# Soal_1.net
KiCad netlist of a schematic drawn in EAGLE
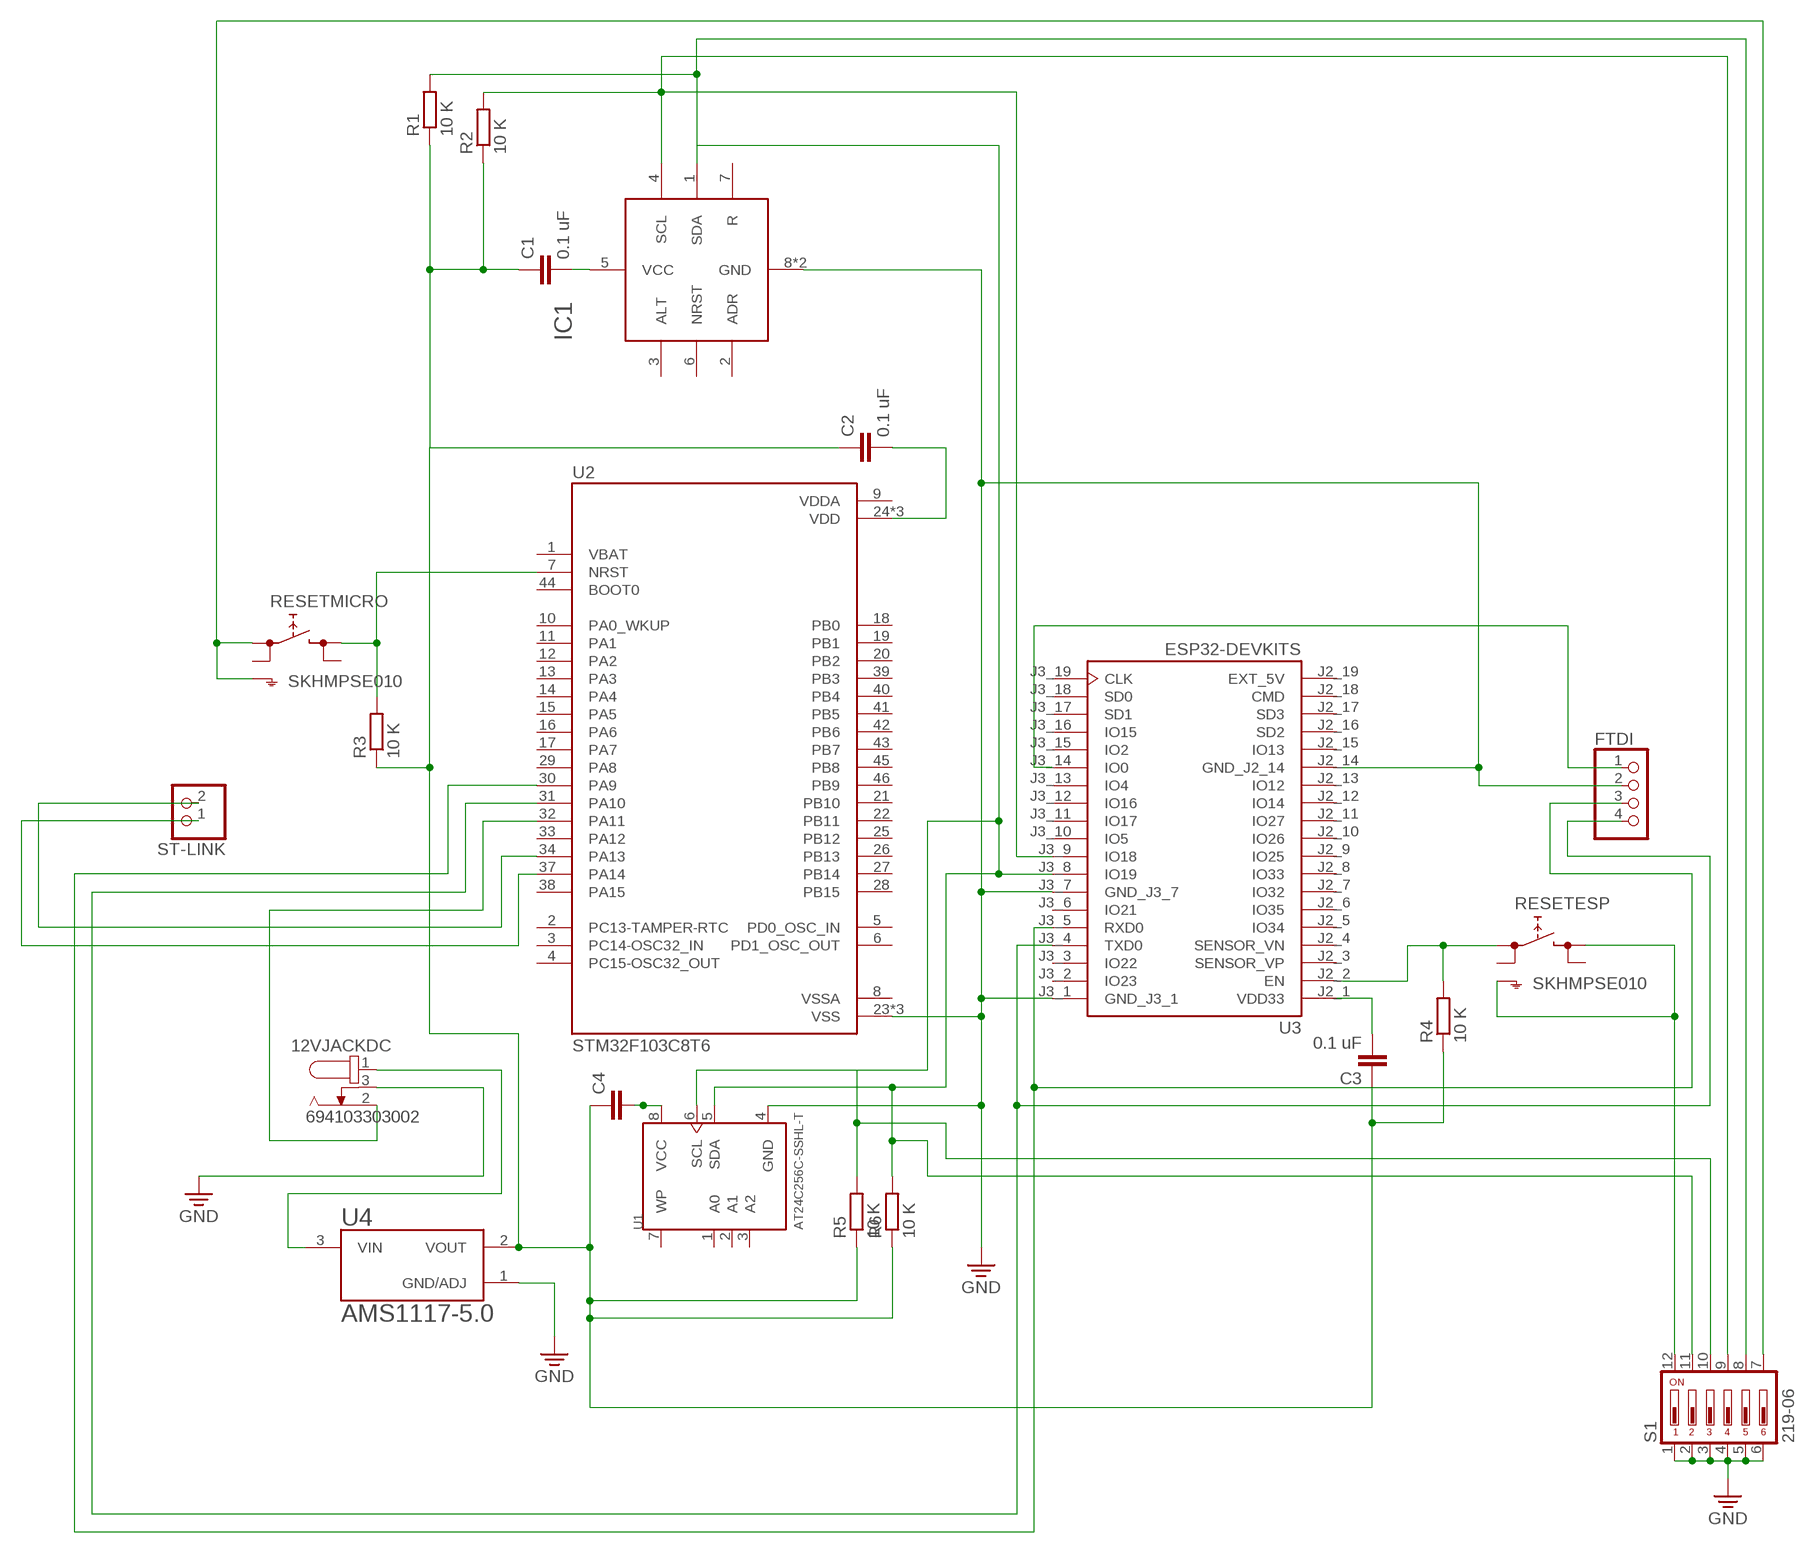
[diagram p0: schematic, sheet 1]

(export (version "E")
  (design (tool "Eeschema 10.0.6"))
  (components
    (comp (ref "12VJACKDC")
      (value "694103303002")
      (footprint "eagle-import:694103303002")
      (fields (field (name "MF") "Wurth Electronics"))
      (libsource (lib "eagle-import") (part "694103303002"))
    )
    (comp (ref "C1")
      (value "0.1 uF")
      (footprint "eagle-import:C5B3.5")
      (libsource (lib "eagle-import") (part "C5/3.5"))
    )
    (comp (ref "C2")
      (value "0.1 uF")
      (footprint "eagle-import:C5B3.5")
      (libsource (lib "eagle-import") (part "C5/3.5"))
    )
    (comp (ref "C3")
      (value "0.1 uF")
      (footprint "eagle-import:C5B3.5")
      (libsource (lib "eagle-import") (part "C5/3.5"))
    )
    (comp (ref "C4")
      (value "C5/3.5")
      (footprint "eagle-import:C5B3.5")
      (libsource (lib "eagle-import") (part "C5/3.5"))
    )
    (comp (ref "FTDI")
      (value "PINHD-1X4")
      (footprint "eagle-import:1X04")
      (libsource (lib "eagle-import") (part "PINHD-1X4"))
    )
    (comp (ref "IC1")
      (value "SHT31")
      (footprint "eagle-import:SON50P250X250X90-9T110X180N")
      (fields (field (name "MF") "Sensirion AG"))
      (libsource (lib "eagle-import") (part "SHT31"))
    )
    (comp (ref "R1")
      (value "10 K")
      (footprint "eagle-import:0207_10")
      (libsource (lib "eagle-import") (part "R-EU_0207/10"))
    )
    (comp (ref "R2")
      (value "10 K")
      (footprint "eagle-import:0207_10")
      (libsource (lib "eagle-import") (part "R-EU_0207/10"))
    )
    (comp (ref "R3")
      (value "10 K")
      (footprint "eagle-import:0207_10")
      (libsource (lib "eagle-import") (part "R-EU_0207/10"))
    )
    (comp (ref "R4")
      (value "10 K")
      (footprint "eagle-import:0207_10")
      (libsource (lib "eagle-import") (part "R-EU_0207/10"))
    )
    (comp (ref "R5")
      (value "10 K")
      (footprint "eagle-import:0207_10")
      (libsource (lib "eagle-import") (part "R-EU_0207/10"))
    )
    (comp (ref "R6")
      (value "10 K")
      (footprint "eagle-import:0207_10")
      (libsource (lib "eagle-import") (part "R-EU_0207/10"))
    )
    (comp (ref "RESETESP")
      (value "SKHMPSE010")
      (footprint "eagle-import:SKHMPXE010")
      (libsource (lib "eagle-import") (part "SKHMPE010S"))
    )
    (comp (ref "RESETMICRO")
      (value "SKHMPSE010")
      (footprint "eagle-import:SKHMPXE010")
      (libsource (lib "eagle-import") (part "SKHMPE010S"))
    )
    (comp (ref "S1")
      (value "219-06")
      (footprint "eagle-import:CTS-219-06")
      (libsource (lib "eagle-import") (part "219-06"))
    )
    (comp (ref "ST-LINK")
      (value "PINHD-1X2")
      (footprint "eagle-import:1X02")
      (libsource (lib "eagle-import") (part "PINHD-1X2"))
    )
    (comp (ref "U1")
      (value "AT24C256C-SSHL-T")
      (footprint "eagle-import:SOIC127P600X175-8N")
      (fields (field (name "MF") "Microchip Technology") (field (name "MP") "AT24C256CSSHLT"))
      (libsource (lib "eagle-import") (part "AT24C256C-SSHL-T"))
    )
    (comp (ref "U2")
      (value "STM32F103C8T6")
      (footprint "eagle-import:QFP50P900X900X160-48N")
      (fields (field (name "MF") "STMicroelectronics"))
      (libsource (lib "eagle-import") (part "STM32F103C8T6"))
    )
    (comp (ref "U3")
      (value "ESP32-DEVKITS")
      (footprint "eagle-import:MODULE_ESP32-DEVKITS")
      (fields (field (name "MF") "Espressif Systems"))
      (libsource (lib "eagle-import") (part "ESP32-DEVKITS"))
    )
    (comp (ref "U4")
      (value "AMS1117-5.0")
      (footprint "eagle-import:SOT229P700X180-4N")
      (fields (field (name "MF") "ams"))
      (libsource (lib "eagle-import") (part "AMS1117-5.0"))
    )
  )
  (nets
    (net (code "1") (name "/EXT_5V") (class "Default")
      (node (ref "U3") (pin "J2_19") (pinfunction "EXT_5V_J2_19") (pintype "power_in"))
    )
    (net (code "2") (name "/VDDA") (class "Default")
      (node (ref "U2") (pin "9") (pinfunction "VDDA_9") (pintype "power_in"))
    )
    (net (code "3") (name "/VSSA") (class "Default")
      (node (ref "U2") (pin "8") (pinfunction "VSSA_8") (pintype "power_in"))
    )
    (net (code "4") (name "GND") (class "Default")
      (node (ref "12VJACKDC") (pin "3") (pinfunction "3_3") (pintype "passive"))
      (node (ref "FTDI") (pin "2") (pinfunction "2_2") (pintype "passive"))
      (node (ref "IC1") (pin "8") (pinfunction "GND_8") (pintype "bidirectional"))
      (node (ref "IC1") (pin "9") (pinfunction "GND_9") (pintype "bidirectional"))
      (node (ref "S1") (pin "1") (pinfunction "1_1") (pintype "passive"))
      (node (ref "S1") (pin "2") (pinfunction "2_2") (pintype "passive"))
      (node (ref "S1") (pin "3") (pinfunction "3_3") (pintype "passive"))
      (node (ref "S1") (pin "4") (pinfunction "4_4") (pintype "passive"))
      (node (ref "S1") (pin "5") (pinfunction "5_5") (pintype "passive"))
      (node (ref "S1") (pin "6") (pinfunction "6_6") (pintype "passive"))
      (node (ref "U1") (pin "4") (pinfunction "GND_4") (pintype "power_in"))
      (node (ref "U2") (pin "23") (pinfunction "VSS_23") (pintype "power_in"))
      (node (ref "U2") (pin "35") (pinfunction "VSS_35") (pintype "power_in"))
      (node (ref "U2") (pin "47") (pinfunction "VSS_47") (pintype "power_in"))
      (node (ref "U3") (pin "J2_14") (pinfunction "GND_J2_14_J2_14") (pintype "power_in"))
      (node (ref "U3") (pin "J3_1") (pinfunction "GND_J3_1_J3_1") (pintype "power_in"))
      (node (ref "U3") (pin "J3_7") (pinfunction "GND_J3_7_J3_7") (pintype "power_in"))
      (node (ref "U4") (pin "1") (pinfunction "GND/ADJ_1") (pintype "power_in"))
    )
    (net (code "5") (name "Net-(C2-Pad2)") (class "Default")
      (node (ref "C2") (pin "2") (pinfunction "2_2") (pintype "passive"))
      (node (ref "U2") (pin "24") (pinfunction "VDD_24") (pintype "power_in"))
      (node (ref "U2") (pin "36") (pinfunction "VDD_36") (pintype "power_in"))
      (node (ref "U2") (pin "48") (pinfunction "VDD_48") (pintype "power_in"))
    )
    (net (code "6") (name "Net-(IC1-SCL)") (class "Default")
      (node (ref "IC1") (pin "4") (pinfunction "SCL_4") (pintype "bidirectional"))
      (node (ref "R2") (pin "2") (pinfunction "2_2") (pintype "passive"))
      (node (ref "S1") (pin "9") (pinfunction "9_9") (pintype "passive"))
      (node (ref "U3") (pin "J3_9") (pinfunction "IO18_J3_9") (pintype "bidirectional"))
    )
    (net (code "7") (name "Net-(IC1-SDA)") (class "Default")
      (node (ref "IC1") (pin "1") (pinfunction "SDA_1") (pintype "bidirectional"))
      (node (ref "R1") (pin "2") (pinfunction "2_2") (pintype "passive"))
      (node (ref "R5") (pin "2") (pinfunction "2_2") (pintype "passive"))
      (node (ref "R6") (pin "2") (pinfunction "2_2") (pintype "passive"))
      (node (ref "S1") (pin "10") (pinfunction "10_10") (pintype "passive"))
      (node (ref "S1") (pin "11") (pinfunction "11_11") (pintype "passive"))
      (node (ref "S1") (pin "8") (pinfunction "8_8") (pintype "passive"))
      (node (ref "U1") (pin "5") (pinfunction "SDA_5") (pintype "bidirectional"))
      (node (ref "U1") (pin "6") (pinfunction "SCL_6") (pintype "input"))
      (node (ref "U3") (pin "J3_8") (pinfunction "IO19_J3_8") (pintype "bidirectional"))
    )
    (net (code "8") (name "Net-(IC1-VCC)") (class "Default")
      (node (ref "C1") (pin "2") (pinfunction "2_2") (pintype "passive"))
      (node (ref "IC1") (pin "5") (pinfunction "VCC_5") (pintype "bidirectional"))
    )
    (net (code "9") (name "Net-(RESETESP-1.1)") (class "Default")
      (node (ref "R4") (pin "2") (pinfunction "2_2") (pintype "passive"))
      (node (ref "RESETESP") (pin "1") (pinfunction "1.1_1") (pintype "passive"))
      (node (ref "U3") (pin "J2_2") (pinfunction "EN_J2_2") (pintype "input"))
    )
    (net (code "10") (name "Net-(RESETESP-2.1)") (class "Default")
      (node (ref "RESETESP") (pin "3") (pinfunction "2.1_3") (pintype "passive"))
      (node (ref "RESETESP") (pin "5") (pinfunction "SH_5") (pintype "passive"))
      (node (ref "S1") (pin "12") (pinfunction "12_12") (pintype "passive"))
    )
    (net (code "11") (name "Net-(RESETMICRO-1.1)") (class "Default")
      (node (ref "RESETMICRO") (pin "1") (pinfunction "1.1_1") (pintype "passive"))
      (node (ref "RESETMICRO") (pin "5") (pinfunction "SH_5") (pintype "passive"))
      (node (ref "S1") (pin "7") (pinfunction "7_7") (pintype "passive"))
    )
    (net (code "12") (name "Net-(RESETMICRO-2.1)") (class "Default")
      (node (ref "R3") (pin "2") (pinfunction "2_2") (pintype "passive"))
      (node (ref "RESETMICRO") (pin "3") (pinfunction "2.1_3") (pintype "passive"))
      (node (ref "U2") (pin "7") (pinfunction "NRST_7") (pintype "input"))
    )
    (net (code "13") (name "Net-(U1-VCC)") (class "Default")
      (node (ref "C4") (pin "2") (pinfunction "2_2") (pintype "passive"))
      (node (ref "U1") (pin "8") (pinfunction "VCC_8") (pintype "power_in"))
    )
    (net (code "14") (name "Net-(U2-PA9)") (class "Default")
      (node (ref "FTDI") (pin "3") (pinfunction "3_3") (pintype "passive"))
      (node (ref "U2") (pin "30") (pinfunction "PA9_30") (pintype "bidirectional"))
      (node (ref "U3") (pin "J3_5") (pinfunction "RXD0_J3_5") (pintype "bidirectional"))
    )
    (net (code "15") (name "Net-(U2-PA10)") (class "Default")
      (node (ref "FTDI") (pin "4") (pinfunction "4_4") (pintype "passive"))
      (node (ref "U2") (pin "31") (pinfunction "PA10_31") (pintype "bidirectional"))
      (node (ref "U3") (pin "J3_4") (pinfunction "TXD0_J3_4") (pintype "bidirectional"))
    )
    (net (code "16") (name "Net-(U2-PA11)") (class "Default")
      (node (ref "12VJACKDC") (pin "2") (pinfunction "2_2") (pintype "passive"))
      (node (ref "U2") (pin "32") (pinfunction "PA11_32") (pintype "bidirectional"))
    )
    (net (code "17") (name "Net-(U2-PA13)") (class "Default")
      (node (ref "ST-LINK") (pin "2") (pinfunction "2_2") (pintype "passive"))
      (node (ref "U2") (pin "34") (pinfunction "PA13_34") (pintype "bidirectional"))
    )
    (net (code "18") (name "Net-(U2-PA14)") (class "Default")
      (node (ref "ST-LINK") (pin "1") (pinfunction "1_1") (pintype "passive"))
      (node (ref "U2") (pin "37") (pinfunction "PA14_37") (pintype "bidirectional"))
    )
    (net (code "19") (name "Net-(U3-IO0)") (class "Default")
      (node (ref "FTDI") (pin "1") (pinfunction "1_1") (pintype "passive"))
      (node (ref "U3") (pin "J3_14") (pinfunction "IO0_J3_14") (pintype "bidirectional"))
    )
    (net (code "20") (name "Net-(U3-VDD33)") (class "Default")
      (node (ref "C3") (pin "2") (pinfunction "2_2") (pintype "passive"))
      (node (ref "U3") (pin "J2_1") (pinfunction "VDD33_J2_1") (pintype "power_in"))
    )
    (net (code "21") (name "Net-(U4-VIN)") (class "Default")
      (node (ref "12VJACKDC") (pin "1") (pinfunction "1_1") (pintype "passive"))
      (node (ref "U4") (pin "3") (pinfunction "VIN_3") (pintype "input"))
    )
    (net (code "22") (name "Net-(U4-VOUT)") (class "Default")
      (node (ref "C1") (pin "1") (pinfunction "1_1") (pintype "passive"))
      (node (ref "C2") (pin "1") (pinfunction "1_1") (pintype "passive"))
      (node (ref "C3") (pin "1") (pinfunction "1_1") (pintype "passive"))
      (node (ref "C4") (pin "1") (pinfunction "1_1") (pintype "passive"))
      (node (ref "R1") (pin "1") (pinfunction "1_1") (pintype "passive"))
      (node (ref "R2") (pin "1") (pinfunction "1_1") (pintype "passive"))
      (node (ref "R3") (pin "1") (pinfunction "1_1") (pintype "passive"))
      (node (ref "R4") (pin "1") (pinfunction "1_1") (pintype "passive"))
      (node (ref "R5") (pin "1") (pinfunction "1_1") (pintype "passive"))
      (node (ref "R6") (pin "1") (pinfunction "1_1") (pintype "passive"))
      (node (ref "U4") (pin "2") (pinfunction "VOUT_2") (pintype "output"))
    )
    (net (code "23") (name "unconnected-(IC1-ADR-Pad2)") (class "Default")
      (node (ref "IC1") (pin "2") (pinfunction "ADR_2") (pintype "bidirectional"))
    )
    (net (code "24") (name "unconnected-(IC1-ALT-Pad3)") (class "Default")
      (node (ref "IC1") (pin "3") (pinfunction "ALT_3") (pintype "bidirectional"))
    )
    (net (code "25") (name "unconnected-(IC1-NRST-Pad6)") (class "Default")
      (node (ref "IC1") (pin "6") (pinfunction "NRST_6") (pintype "bidirectional"))
    )
    (net (code "26") (name "unconnected-(IC1-R-Pad7)") (class "Default")
      (node (ref "IC1") (pin "7") (pinfunction "R_7") (pintype "bidirectional"))
    )
    (net (code "27") (name "unconnected-(RESETESP-1.2-Pad2)") (class "Default")
      (node (ref "RESETESP") (pin "2") (pinfunction "1.2_2") (pintype "passive"))
    )
    (net (code "28") (name "unconnected-(RESETESP-2.2-Pad4)") (class "Default")
      (node (ref "RESETESP") (pin "4") (pinfunction "2.2_4") (pintype "passive"))
    )
    (net (code "29") (name "unconnected-(RESETMICRO-1.2-Pad2)") (class "Default")
      (node (ref "RESETMICRO") (pin "2") (pinfunction "1.2_2") (pintype "passive"))
    )
    (net (code "30") (name "unconnected-(RESETMICRO-2.2-Pad4)") (class "Default")
      (node (ref "RESETMICRO") (pin "4") (pinfunction "2.2_4") (pintype "passive"))
    )
    (net (code "31") (name "unconnected-(U1-A0-Pad1)") (class "Default")
      (node (ref "U1") (pin "1") (pinfunction "A0_1") (pintype "input"))
    )
    (net (code "32") (name "unconnected-(U1-A1-Pad2)") (class "Default")
      (node (ref "U1") (pin "2") (pinfunction "A1_2") (pintype "input"))
    )
    (net (code "33") (name "unconnected-(U1-A2-Pad3)") (class "Default")
      (node (ref "U1") (pin "3") (pinfunction "A2_3") (pintype "input"))
    )
    (net (code "34") (name "unconnected-(U1-WP-Pad7)") (class "Default")
      (node (ref "U1") (pin "7") (pinfunction "WP_7") (pintype "input"))
    )
    (net (code "35") (name "unconnected-(U2-BOOT0-Pad44)") (class "Default")
      (node (ref "U2") (pin "44") (pinfunction "BOOT0_44") (pintype "input"))
    )
    (net (code "36") (name "unconnected-(U2-PA0_WKUP-Pad10)") (class "Default")
      (node (ref "U2") (pin "10") (pinfunction "PA0_WKUP_10") (pintype "bidirectional"))
    )
    (net (code "37") (name "unconnected-(U2-PA1-Pad11)") (class "Default")
      (node (ref "U2") (pin "11") (pinfunction "PA1_11") (pintype "bidirectional"))
    )
    (net (code "38") (name "unconnected-(U2-PA2-Pad12)") (class "Default")
      (node (ref "U2") (pin "12") (pinfunction "PA2_12") (pintype "bidirectional"))
    )
    (net (code "39") (name "unconnected-(U2-PA3-Pad13)") (class "Default")
      (node (ref "U2") (pin "13") (pinfunction "PA3_13") (pintype "bidirectional"))
    )
    (net (code "40") (name "unconnected-(U2-PA4-Pad14)") (class "Default")
      (node (ref "U2") (pin "14") (pinfunction "PA4_14") (pintype "bidirectional"))
    )
    (net (code "41") (name "unconnected-(U2-PA5-Pad15)") (class "Default")
      (node (ref "U2") (pin "15") (pinfunction "PA5_15") (pintype "bidirectional"))
    )
    (net (code "42") (name "unconnected-(U2-PA6-Pad16)") (class "Default")
      (node (ref "U2") (pin "16") (pinfunction "PA6_16") (pintype "bidirectional"))
    )
    (net (code "43") (name "unconnected-(U2-PA7-Pad17)") (class "Default")
      (node (ref "U2") (pin "17") (pinfunction "PA7_17") (pintype "bidirectional"))
    )
    (net (code "44") (name "unconnected-(U2-PA8-Pad29)") (class "Default")
      (node (ref "U2") (pin "29") (pinfunction "PA8_29") (pintype "bidirectional"))
    )
    (net (code "45") (name "unconnected-(U2-PA12-Pad33)") (class "Default")
      (node (ref "U2") (pin "33") (pinfunction "PA12_33") (pintype "bidirectional"))
    )
    (net (code "46") (name "unconnected-(U2-PA15-Pad38)") (class "Default")
      (node (ref "U2") (pin "38") (pinfunction "PA15_38") (pintype "bidirectional"))
    )
    (net (code "47") (name "unconnected-(U2-PB0-Pad18)") (class "Default")
      (node (ref "U2") (pin "18") (pinfunction "PB0_18") (pintype "bidirectional"))
    )
    (net (code "48") (name "unconnected-(U2-PB1-Pad19)") (class "Default")
      (node (ref "U2") (pin "19") (pinfunction "PB1_19") (pintype "bidirectional"))
    )
    (net (code "49") (name "unconnected-(U2-PB2-Pad20)") (class "Default")
      (node (ref "U2") (pin "20") (pinfunction "PB2_20") (pintype "bidirectional"))
    )
    (net (code "50") (name "unconnected-(U2-PB3-Pad39)") (class "Default")
      (node (ref "U2") (pin "39") (pinfunction "PB3_39") (pintype "bidirectional"))
    )
    (net (code "51") (name "unconnected-(U2-PB4-Pad40)") (class "Default")
      (node (ref "U2") (pin "40") (pinfunction "PB4_40") (pintype "bidirectional"))
    )
    (net (code "52") (name "unconnected-(U2-PB5-Pad41)") (class "Default")
      (node (ref "U2") (pin "41") (pinfunction "PB5_41") (pintype "bidirectional"))
    )
    (net (code "53") (name "unconnected-(U2-PB6-Pad42)") (class "Default")
      (node (ref "U2") (pin "42") (pinfunction "PB6_42") (pintype "bidirectional"))
    )
    (net (code "54") (name "unconnected-(U2-PB7-Pad43)") (class "Default")
      (node (ref "U2") (pin "43") (pinfunction "PB7_43") (pintype "bidirectional"))
    )
    (net (code "55") (name "unconnected-(U2-PB8-Pad45)") (class "Default")
      (node (ref "U2") (pin "45") (pinfunction "PB8_45") (pintype "bidirectional"))
    )
    (net (code "56") (name "unconnected-(U2-PB9-Pad46)") (class "Default")
      (node (ref "U2") (pin "46") (pinfunction "PB9_46") (pintype "bidirectional"))
    )
    (net (code "57") (name "unconnected-(U2-PB10-Pad21)") (class "Default")
      (node (ref "U2") (pin "21") (pinfunction "PB10_21") (pintype "bidirectional"))
    )
    (net (code "58") (name "unconnected-(U2-PB11-Pad22)") (class "Default")
      (node (ref "U2") (pin "22") (pinfunction "PB11_22") (pintype "bidirectional"))
    )
    (net (code "59") (name "unconnected-(U2-PB12-Pad25)") (class "Default")
      (node (ref "U2") (pin "25") (pinfunction "PB12_25") (pintype "bidirectional"))
    )
    (net (code "60") (name "unconnected-(U2-PB13-Pad26)") (class "Default")
      (node (ref "U2") (pin "26") (pinfunction "PB13_26") (pintype "bidirectional"))
    )
    (net (code "61") (name "unconnected-(U2-PB14-Pad27)") (class "Default")
      (node (ref "U2") (pin "27") (pinfunction "PB14_27") (pintype "bidirectional"))
    )
    (net (code "62") (name "unconnected-(U2-PB15-Pad28)") (class "Default")
      (node (ref "U2") (pin "28") (pinfunction "PB15_28") (pintype "bidirectional"))
    )
    (net (code "63") (name "unconnected-(U2-PC13-TAMPER-RTC-Pad2)") (class "Default")
      (node (ref "U2") (pin "2") (pinfunction "PC13-TAMPER-RTC_2") (pintype "bidirectional"))
    )
    (net (code "64") (name "unconnected-(U2-PC14-OSC32_IN-Pad3)") (class "Default")
      (node (ref "U2") (pin "3") (pinfunction "PC14-OSC32_IN_3") (pintype "bidirectional"))
    )
    (net (code "65") (name "unconnected-(U2-PC15-OSC32_OUT-Pad4)") (class "Default")
      (node (ref "U2") (pin "4") (pinfunction "PC15-OSC32_OUT_4") (pintype "bidirectional"))
    )
    (net (code "66") (name "unconnected-(U2-PD0_OSC_IN-Pad5)") (class "Default")
      (node (ref "U2") (pin "5") (pinfunction "PD0_OSC_IN_5") (pintype "bidirectional"))
    )
    (net (code "67") (name "unconnected-(U2-PD1_OSC_OUT-Pad6)") (class "Default")
      (node (ref "U2") (pin "6") (pinfunction "PD1_OSC_OUT_6") (pintype "bidirectional"))
    )
    (net (code "68") (name "unconnected-(U2-VBAT-Pad1)") (class "Default")
      (node (ref "U2") (pin "1") (pinfunction "VBAT_1") (pintype "bidirectional"))
    )
    (net (code "69") (name "unconnected-(U3-CLK-PadJ3_19)") (class "Default")
      (node (ref "U3") (pin "J3_19") (pinfunction "CLK_J3_19") (pintype "bidirectional"))
    )
    (net (code "70") (name "unconnected-(U3-CMD-PadJ2_18)") (class "Default")
      (node (ref "U3") (pin "J2_18") (pinfunction "CMD_J2_18") (pintype "bidirectional"))
    )
    (net (code "71") (name "unconnected-(U3-IO2-PadJ3_15)") (class "Default")
      (node (ref "U3") (pin "J3_15") (pinfunction "IO2_J3_15") (pintype "bidirectional"))
    )
    (net (code "72") (name "unconnected-(U3-IO4-PadJ3_13)") (class "Default")
      (node (ref "U3") (pin "J3_13") (pinfunction "IO4_J3_13") (pintype "bidirectional"))
    )
    (net (code "73") (name "unconnected-(U3-IO5-PadJ3_10)") (class "Default")
      (node (ref "U3") (pin "J3_10") (pinfunction "IO5_J3_10") (pintype "bidirectional"))
    )
    (net (code "74") (name "unconnected-(U3-IO12-PadJ2_13)") (class "Default")
      (node (ref "U3") (pin "J2_13") (pinfunction "IO12_J2_13") (pintype "bidirectional"))
    )
    (net (code "75") (name "unconnected-(U3-IO13-PadJ2_15)") (class "Default")
      (node (ref "U3") (pin "J2_15") (pinfunction "IO13_J2_15") (pintype "bidirectional"))
    )
    (net (code "76") (name "unconnected-(U3-IO14-PadJ2_12)") (class "Default")
      (node (ref "U3") (pin "J2_12") (pinfunction "IO14_J2_12") (pintype "bidirectional"))
    )
    (net (code "77") (name "unconnected-(U3-IO15-PadJ3_16)") (class "Default")
      (node (ref "U3") (pin "J3_16") (pinfunction "IO15_J3_16") (pintype "bidirectional"))
    )
    (net (code "78") (name "unconnected-(U3-IO16-PadJ3_12)") (class "Default")
      (node (ref "U3") (pin "J3_12") (pinfunction "IO16_J3_12") (pintype "bidirectional"))
    )
    (net (code "79") (name "unconnected-(U3-IO17-PadJ3_11)") (class "Default")
      (node (ref "U3") (pin "J3_11") (pinfunction "IO17_J3_11") (pintype "bidirectional"))
    )
    (net (code "80") (name "unconnected-(U3-IO21-PadJ3_6)") (class "Default")
      (node (ref "U3") (pin "J3_6") (pinfunction "IO21_J3_6") (pintype "bidirectional"))
    )
    (net (code "81") (name "unconnected-(U3-IO22-PadJ3_3)") (class "Default")
      (node (ref "U3") (pin "J3_3") (pinfunction "IO22_J3_3") (pintype "bidirectional"))
    )
    (net (code "82") (name "unconnected-(U3-IO23-PadJ3_2)") (class "Default")
      (node (ref "U3") (pin "J3_2") (pinfunction "IO23_J3_2") (pintype "bidirectional"))
    )
    (net (code "83") (name "unconnected-(U3-IO25-PadJ2_9)") (class "Default")
      (node (ref "U3") (pin "J2_9") (pinfunction "IO25_J2_9") (pintype "bidirectional"))
    )
    (net (code "84") (name "unconnected-(U3-IO26-PadJ2_10)") (class "Default")
      (node (ref "U3") (pin "J2_10") (pinfunction "IO26_J2_10") (pintype "bidirectional"))
    )
    (net (code "85") (name "unconnected-(U3-IO27-PadJ2_11)") (class "Default")
      (node (ref "U3") (pin "J2_11") (pinfunction "IO27_J2_11") (pintype "bidirectional"))
    )
    (net (code "86") (name "unconnected-(U3-IO32-PadJ2_7)") (class "Default")
      (node (ref "U3") (pin "J2_7") (pinfunction "IO32_J2_7") (pintype "bidirectional"))
    )
    (net (code "87") (name "unconnected-(U3-IO33-PadJ2_8)") (class "Default")
      (node (ref "U3") (pin "J2_8") (pinfunction "IO33_J2_8") (pintype "bidirectional"))
    )
    (net (code "88") (name "unconnected-(U3-IO34-PadJ2_5)") (class "Default")
      (node (ref "U3") (pin "J2_5") (pinfunction "IO34_J2_5") (pintype "bidirectional"))
    )
    (net (code "89") (name "unconnected-(U3-IO35-PadJ2_6)") (class "Default")
      (node (ref "U3") (pin "J2_6") (pinfunction "IO35_J2_6") (pintype "bidirectional"))
    )
    (net (code "90") (name "unconnected-(U3-SD0-PadJ3_18)") (class "Default")
      (node (ref "U3") (pin "J3_18") (pinfunction "SD0_J3_18") (pintype "bidirectional"))
    )
    (net (code "91") (name "unconnected-(U3-SD1-PadJ3_17)") (class "Default")
      (node (ref "U3") (pin "J3_17") (pinfunction "SD1_J3_17") (pintype "bidirectional"))
    )
    (net (code "92") (name "unconnected-(U3-SD2-PadJ2_16)") (class "Default")
      (node (ref "U3") (pin "J2_16") (pinfunction "SD2_J2_16") (pintype "bidirectional"))
    )
    (net (code "93") (name "unconnected-(U3-SD3-PadJ2_17)") (class "Default")
      (node (ref "U3") (pin "J2_17") (pinfunction "SD3_J2_17") (pintype "bidirectional"))
    )
    (net (code "94") (name "unconnected-(U3-SENSOR_VN-PadJ2_4)") (class "Default")
      (node (ref "U3") (pin "J2_4") (pinfunction "SENSOR_VN_J2_4") (pintype "bidirectional"))
    )
    (net (code "95") (name "unconnected-(U3-SENSOR_VP-PadJ2_3)") (class "Default")
      (node (ref "U3") (pin "J2_3") (pinfunction "SENSOR_VP_J2_3") (pintype "bidirectional"))
    )
  )
)
